# ESP8266_RFID_Schematic.net
KiCad netlist of a schematic drawn in EAGLE
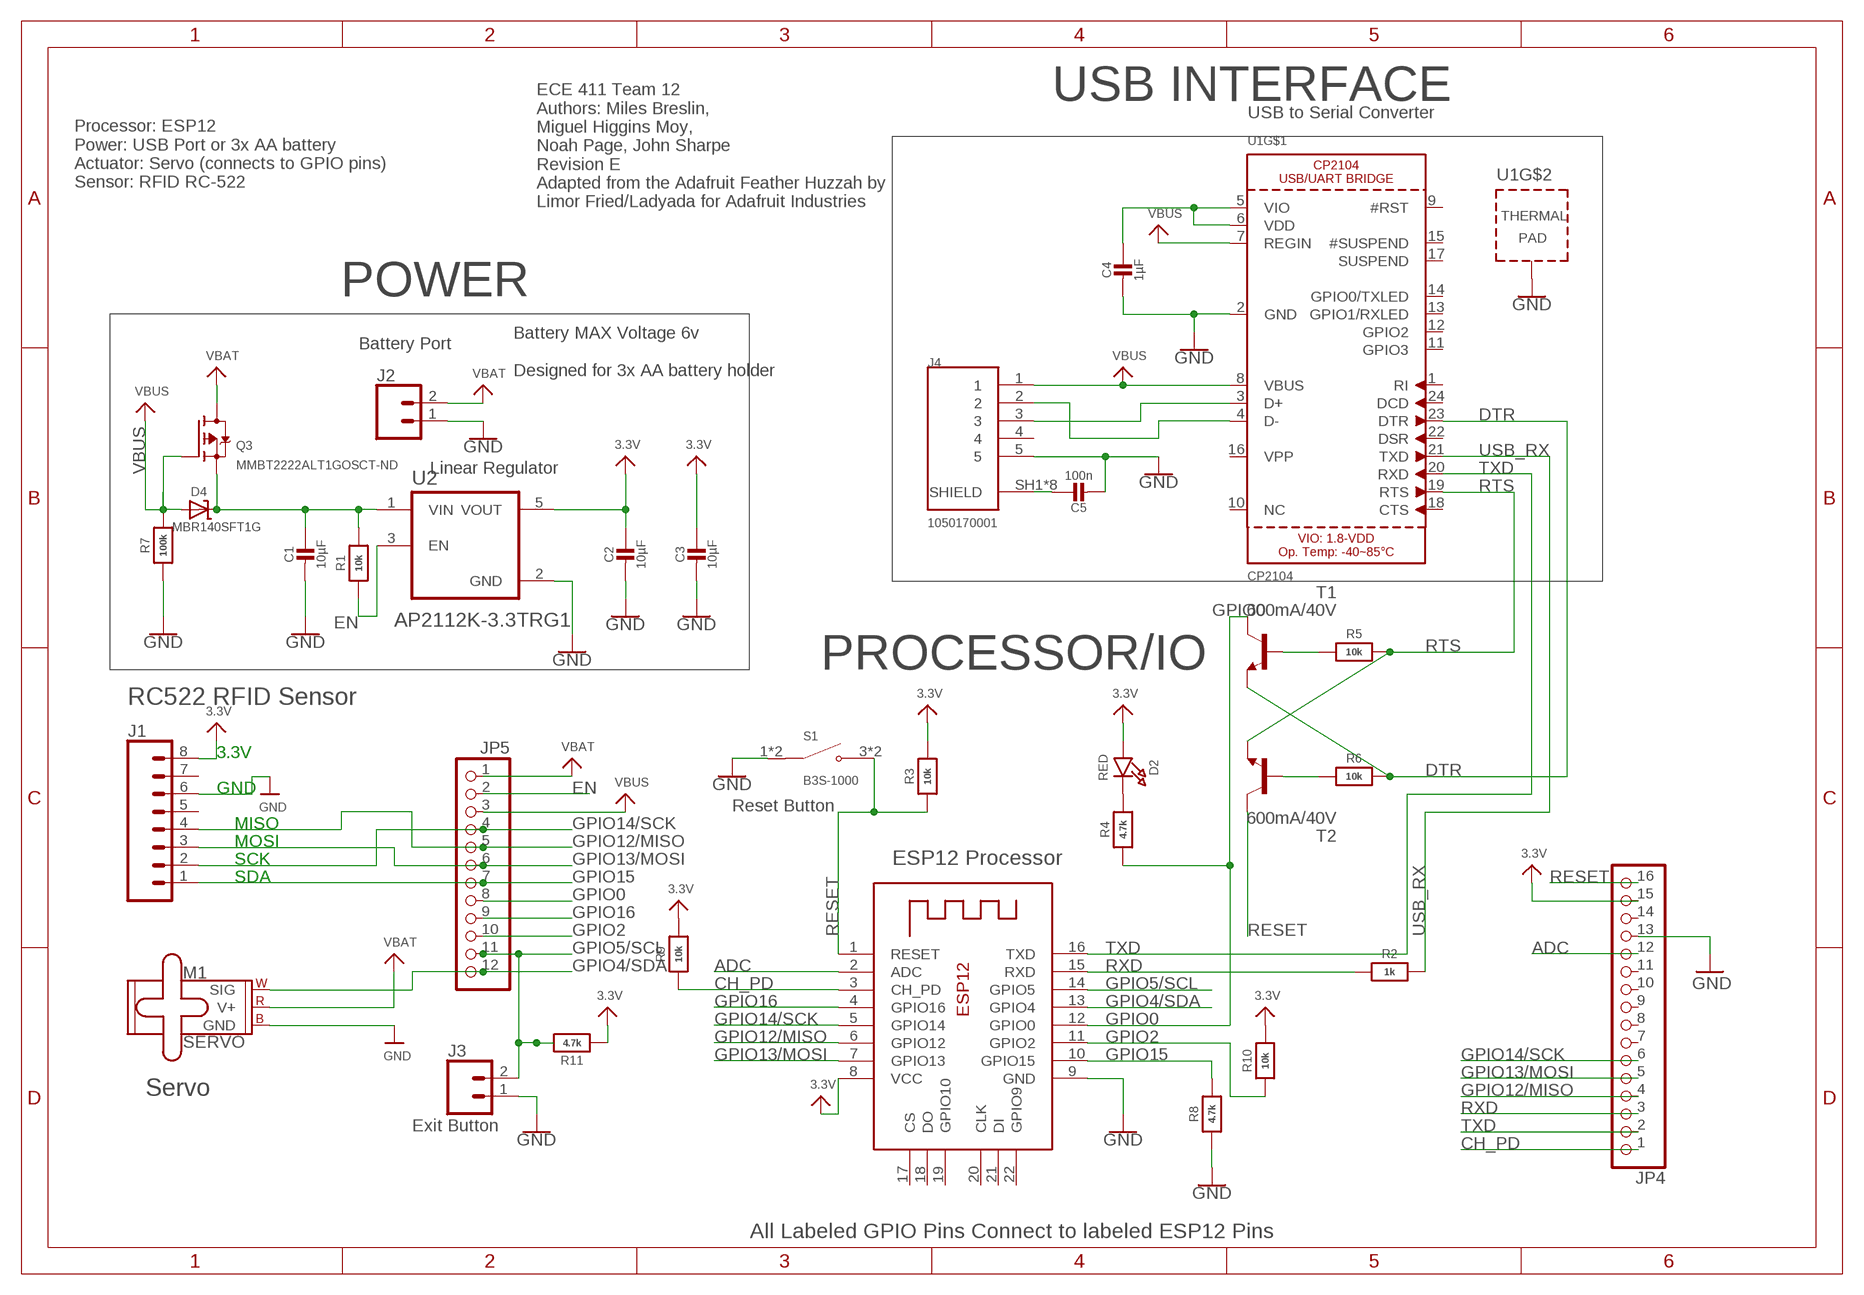
[diagram p0: schematic, sheet 1]

(export (version "E")
  (design (tool "Eeschema 10.0.6"))
  (components
    (comp (ref "C1")
      (value "10µF")
      (footprint "eagle-import:0603-MINI")
      (libsource (lib "eagle-import") (part "CAP_CERAMIC0603MINI"))
    )
    (comp (ref "C2")
      (value "10µF")
      (footprint "eagle-import:0603-MINI")
      (libsource (lib "eagle-import") (part "CAP_CERAMIC0603MINI"))
    )
    (comp (ref "C3")
      (value "10µF")
      (footprint "eagle-import:0603-MINI")
      (libsource (lib "eagle-import") (part "CAP_CERAMIC0603MINI"))
    )
    (comp (ref "C4")
      (value "1µF")
      (footprint "eagle-import:0603-MINI")
      (libsource (lib "eagle-import") (part "CAP_CERAMIC0603MINI"))
    )
    (comp (ref "C5")
      (value "100n")
      (footprint "eagle-import:0603-MINI")
      (libsource (lib "eagle-import") (part "CAP_CERAMIC0603MINI"))
    )
    (comp (ref "D2")
      (value "RED")
      (footprint "eagle-import:CHIPLED_0603")
      (libsource (lib "eagle-import") (part "LED0603"))
    )
    (comp (ref "D4")
      (value "MBR140SFT1G")
      (footprint "eagle-import:SOD-123")
      (libsource (lib "eagle-import") (part "DIODE-SCHOTTKYSOD-123"))
    )
    (comp (ref "J1")
      (value "CONN_08\"")
      (footprint "eagle-import:1X08")
      (libsource (lib "eagle-import") (part "CONN_08{dblquote}"))
    )
    (comp (ref "J2")
      (value "CONN_02")
      (footprint "eagle-import:1X02")
      (libsource (lib "eagle-import") (part "CONN_02"))
    )
    (comp (ref "J3")
      (value "CONN_02")
      (footprint "eagle-import:1X02")
      (libsource (lib "eagle-import") (part "CONN_02"))
    )
    (comp (ref "J4")
      (value "1050170001")
      (footprint "eagle-import:MOLEX_1050170001")
      (fields (field (name "DIGI-KEY_PART_NUMBER") "WM1399CT-ND") (field (name "MF") "Molex"))
      (libsource (lib "eagle-import") (part "1050170001"))
    )
    (comp (ref "JP4")
      (value "HEADER-1X16ROUND")
      (footprint "eagle-import:1X16_ROUND")
      (libsource (lib "eagle-import") (part "HEADER-1X16ROUND"))
    )
    (comp (ref "JP5")
      (value "HEADER-1X12")
      (footprint "eagle-import:1X12_ROUND")
      (libsource (lib "eagle-import") (part "HEADER-1X12"))
    )
    (comp (ref "M1")
      (value "SERVO")
      (footprint "eagle-import:1X03")
      (libsource (lib "eagle-import") (part "SERVO"))
    )
    (comp (ref "Q3")
      (value "MMBT2222ALT1GOSCT-ND")
      (footprint "eagle-import:SOT23-R")
      (libsource (lib "eagle-import") (part "MOSFET-P"))
    )
    (comp (ref "R1")
      (value "10k")
      (footprint "eagle-import:0603-MINI")
      (libsource (lib "eagle-import") (part "RESISTOR0603MINI"))
    )
    (comp (ref "R2")
      (value "1k")
      (footprint "eagle-import:0603-MINI")
      (libsource (lib "eagle-import") (part "RESISTOR0603MINI"))
    )
    (comp (ref "R3")
      (value "10k")
      (footprint "eagle-import:0603-MINI")
      (libsource (lib "eagle-import") (part "RESISTOR0603MINI"))
    )
    (comp (ref "R4")
      (value "4.7k")
      (footprint "eagle-import:0603-MINI")
      (libsource (lib "eagle-import") (part "RESISTOR0603MINI"))
    )
    (comp (ref "R5")
      (value "10k")
      (footprint "eagle-import:0603-MINI")
      (libsource (lib "eagle-import") (part "RESISTOR0603MINI"))
    )
    (comp (ref "R6")
      (value "10k")
      (footprint "eagle-import:0603-MINI")
      (libsource (lib "eagle-import") (part "RESISTOR0603MINI"))
    )
    (comp (ref "R7")
      (value "100k")
      (footprint "eagle-import:0603-MINI")
      (libsource (lib "eagle-import") (part "RESISTOR0603MINI"))
    )
    (comp (ref "R8")
      (value "4.7k")
      (footprint "eagle-import:0603-MINI")
      (libsource (lib "eagle-import") (part "RESISTOR0603MINI"))
    )
    (comp (ref "R9")
      (value "10k")
      (footprint "eagle-import:0603-MINI")
      (libsource (lib "eagle-import") (part "RESISTOR0603MINI"))
    )
    (comp (ref "R10")
      (value "10k")
      (footprint "eagle-import:0603-MINI")
      (libsource (lib "eagle-import") (part "RESISTOR0603MINI"))
    )
    (comp (ref "R11")
      (value "4.7k")
      (footprint "eagle-import:0603-MINI")
      (libsource (lib "eagle-import") (part "RESISTOR0603MINI"))
    )
    (comp (ref "S1")
      (value "B3S-1000")
      (footprint "eagle-import:SW_B3S-1000")
      (fields (field (name "DIGI-KEY_PART_NUMBER") "SW836TR-ND") (field (name "MF") "Omron"))
      (libsource (lib "eagle-import") (part "B3S-1000"))
    )
    (comp (ref "T1")
      (value "600mA/40V")
      (footprint "eagle-import:SOT23-3")
      (libsource (lib "eagle-import") (part "TRANS_NPN-MMBT2222AL"))
    )
    (comp (ref "T2")
      (value "600mA/40V")
      (footprint "eagle-import:SOT23-3")
      (libsource (lib "eagle-import") (part "TRANS_NPN-MMBT2222AL"))
    )
    (comp (ref "U1")
      (value "CP2104")
      (footprint "eagle-import:QFN24_4MM_SMSC")
      (libsource (lib "eagle-import") (part "CP2104"))
    )
    (comp (ref "U2")
      (value "AP2112K-3.3TRG1")
      (footprint "eagle-import:SOT95P285X140-5N")
      (fields
        (field (name "DIGI-KEY_PART_NUMBER") "AP2112K-3.3TRG1DICT-ND")
        (field (name "MF") "Diodes Inc.")
      )
      (libsource (lib "eagle-import") (part "AP2112K-3.3TRG1"))
    )
    (comp (ref "X1")
      (value "ESP-12E")
      (footprint "eagle-import:ESP-12E")
      (libsource (lib "eagle-import") (part "ESP-12E"))
    )
  )
  (nets
    (net (code "1") (name "/ADC") (class "Default")
      (node (ref "JP4") (pin "12") (pinfunction "12_12") (pintype "passive"))
      (node (ref "X1") (pin "2") (pinfunction "ADC_2") (pintype "passive"))
    )
    (net (code "2") (name "/CH_PD") (class "Default")
      (node (ref "JP4") (pin "1") (pinfunction "1_1") (pintype "passive"))
      (node (ref "R9") (pin "1") (pinfunction "1_1") (pintype "passive"))
      (node (ref "X1") (pin "3") (pinfunction "CH_PD_3") (pintype "input"))
    )
    (net (code "3") (name "/DTR") (class "Default")
      (node (ref "R6") (pin "2") (pinfunction "2_2") (pintype "passive"))
      (node (ref "T1") (pin "2") (pinfunction "E_2") (pintype "passive"))
      (node (ref "U1") (pin "23") (pinfunction "DTR_23") (pintype "output"))
    )
    (net (code "4") (name "/EN") (class "Default")
      (node (ref "JP5") (pin "2") (pinfunction "2_2") (pintype "passive"))
      (node (ref "R1") (pin "1") (pinfunction "1_1") (pintype "passive"))
      (node (ref "U2") (pin "3") (pinfunction "EN_3") (pintype "input"))
    )
    (net (code "5") (name "/GPIO0") (class "Default")
      (node (ref "JP5") (pin "8") (pinfunction "8_8") (pintype "passive"))
      (node (ref "R4") (pin "1") (pinfunction "1_1") (pintype "passive"))
      (node (ref "T1") (pin "3") (pinfunction "C_3") (pintype "passive"))
      (node (ref "X1") (pin "12") (pinfunction "GPIO0_12") (pintype "bidirectional"))
    )
    (net (code "6") (name "/GPIO2") (class "Default")
      (node (ref "JP5") (pin "10") (pinfunction "10_10") (pintype "passive"))
      (node (ref "R10") (pin "1") (pinfunction "1_1") (pintype "passive"))
      (node (ref "X1") (pin "11") (pinfunction "GPIO2_11") (pintype "bidirectional"))
    )
    (net (code "7") (name "/GPIO4{slash}SDA") (class "Default")
      (node (ref "JP5") (pin "12") (pinfunction "12_12") (pintype "passive"))
      (node (ref "M1") (pin "1") (pinfunction "SIG_1") (pintype "bidirectional"))
      (node (ref "X1") (pin "13") (pinfunction "GPIO4_13") (pintype "bidirectional"))
    )
    (net (code "8") (name "/GPIO5{slash}SCL") (class "Default")
      (node (ref "J3") (pin "2") (pinfunction "2_2") (pintype "passive"))
      (node (ref "JP5") (pin "11") (pinfunction "11_11") (pintype "passive"))
      (node (ref "R11") (pin "2") (pinfunction "2_2") (pintype "passive"))
      (node (ref "X1") (pin "14") (pinfunction "GPIO5_14") (pintype "bidirectional"))
    )
    (net (code "9") (name "/GPIO12{slash}MISO") (class "Default")
      (node (ref "J1") (pin "4") (pinfunction "4_4") (pintype "passive"))
      (node (ref "JP4") (pin "4") (pinfunction "4_4") (pintype "passive"))
      (node (ref "JP5") (pin "5") (pinfunction "5_5") (pintype "passive"))
      (node (ref "X1") (pin "6") (pinfunction "GPIO12_6") (pintype "bidirectional"))
    )
    (net (code "10") (name "/GPIO13{slash}MOSI") (class "Default")
      (node (ref "J1") (pin "3") (pinfunction "3_3") (pintype "passive"))
      (node (ref "JP4") (pin "5") (pinfunction "5_5") (pintype "passive"))
      (node (ref "JP5") (pin "6") (pinfunction "6_6") (pintype "passive"))
      (node (ref "X1") (pin "7") (pinfunction "GPIO13_7") (pintype "bidirectional"))
    )
    (net (code "11") (name "/GPIO14{slash}SCK") (class "Default")
      (node (ref "J1") (pin "2") (pinfunction "2_2") (pintype "passive"))
      (node (ref "JP4") (pin "6") (pinfunction "6_6") (pintype "passive"))
      (node (ref "JP5") (pin "4") (pinfunction "4_4") (pintype "passive"))
      (node (ref "X1") (pin "5") (pinfunction "GPIO14_5") (pintype "bidirectional"))
    )
    (net (code "12") (name "/GPIO15") (class "Default")
      (node (ref "J1") (pin "1") (pinfunction "1_1") (pintype "passive"))
      (node (ref "JP5") (pin "7") (pinfunction "7_7") (pintype "passive"))
      (node (ref "R8") (pin "2") (pinfunction "2_2") (pintype "passive"))
      (node (ref "X1") (pin "10") (pinfunction "GPIO15_10") (pintype "bidirectional"))
    )
    (net (code "13") (name "/GPIO16") (class "Default")
      (node (ref "JP5") (pin "9") (pinfunction "9_9") (pintype "passive"))
      (node (ref "X1") (pin "4") (pinfunction "GPIO16_4") (pintype "bidirectional"))
    )
    (net (code "14") (name "/RESET") (class "Default")
      (node (ref "JP4") (pin "16") (pinfunction "16_16") (pintype "passive"))
      (node (ref "R3") (pin "1") (pinfunction "1_1") (pintype "passive"))
      (node (ref "S1") (pin "3") (pinfunction "NO_3") (pintype "passive"))
      (node (ref "S1") (pin "4") (pinfunction "NO_4") (pintype "passive"))
      (node (ref "T2") (pin "3") (pinfunction "C_3") (pintype "passive"))
      (node (ref "X1") (pin "1") (pinfunction "RESET_1") (pintype "input"))
    )
    (net (code "15") (name "/RTS") (class "Default")
      (node (ref "R5") (pin "2") (pinfunction "2_2") (pintype "passive"))
      (node (ref "T2") (pin "2") (pinfunction "E_2") (pintype "passive"))
      (node (ref "U1") (pin "19") (pinfunction "RTS_19") (pintype "output"))
    )
    (net (code "16") (name "/RXD") (class "Default")
      (node (ref "JP4") (pin "3") (pinfunction "3_3") (pintype "passive"))
      (node (ref "R2") (pin "1") (pinfunction "1_1") (pintype "passive"))
      (node (ref "X1") (pin "15") (pinfunction "RXD_15") (pintype "input"))
    )
    (net (code "17") (name "/TXD") (class "Default")
      (node (ref "JP4") (pin "2") (pinfunction "2_2") (pintype "passive"))
      (node (ref "U1") (pin "20") (pinfunction "RXD_20") (pintype "input"))
      (node (ref "X1") (pin "16") (pinfunction "TXD_16") (pintype "output"))
    )
    (net (code "18") (name "/USB_RX") (class "Default")
      (node (ref "R2") (pin "2") (pinfunction "2_2") (pintype "passive"))
      (node (ref "U1") (pin "21") (pinfunction "TXD_21") (pintype "output"))
    )
    (net (code "19") (name "3.3V") (class "Default")
      (node (ref "C2") (pin "1") (pinfunction "1_1") (pintype "passive"))
      (node (ref "C3") (pin "1") (pinfunction "1_1") (pintype "passive"))
      (node (ref "D2") (pin "A") (pinfunction "A_A") (pintype "passive"))
      (node (ref "J1") (pin "8") (pinfunction "8_8") (pintype "passive"))
      (node (ref "JP4") (pin "15") (pinfunction "15_15") (pintype "passive"))
      (node (ref "R10") (pin "2") (pinfunction "2_2") (pintype "passive"))
      (node (ref "R11") (pin "1") (pinfunction "1_1") (pintype "passive"))
      (node (ref "R3") (pin "2") (pinfunction "2_2") (pintype "passive"))
      (node (ref "R9") (pin "2") (pinfunction "2_2") (pintype "passive"))
      (node (ref "U2") (pin "5") (pinfunction "VOUT_5") (pintype "power_in"))
      (node (ref "X1") (pin "8") (pinfunction "VCC_8") (pintype "power_in"))
    )
    (net (code "20") (name "GND") (class "Default")
      (node (ref "C1") (pin "2") (pinfunction "2_2") (pintype "passive"))
      (node (ref "C2") (pin "2") (pinfunction "2_2") (pintype "passive"))
      (node (ref "C3") (pin "2") (pinfunction "2_2") (pintype "passive"))
      (node (ref "C4") (pin "2") (pinfunction "2_2") (pintype "passive"))
      (node (ref "C5") (pin "2") (pinfunction "2_2") (pintype "passive"))
      (node (ref "J1") (pin "6") (pinfunction "6_6") (pintype "passive"))
      (node (ref "J2") (pin "1") (pinfunction "1_1") (pintype "passive"))
      (node (ref "J3") (pin "1") (pinfunction "1_1") (pintype "passive"))
      (node (ref "J4") (pin "5") (pinfunction "5_5") (pintype "passive"))
      (node (ref "JP4") (pin "13") (pinfunction "13_13") (pintype "passive"))
      (node (ref "M1") (pin "3") (pinfunction "GND_3") (pintype "bidirectional"))
      (node (ref "R7") (pin "1") (pinfunction "1_1") (pintype "passive"))
      (node (ref "R8") (pin "1") (pinfunction "1_1") (pintype "passive"))
      (node (ref "S1") (pin "1") (pinfunction "COM_1") (pintype "passive"))
      (node (ref "S1") (pin "2") (pinfunction "COM_2") (pintype "passive"))
      (node (ref "U1") (pin "2") (pinfunction "GND_2") (pintype "power_in"))
      (node (ref "U1") (pin "THERM") (pinfunction "TP_THERM") (pintype "power_in"))
      (node (ref "U2") (pin "2") (pinfunction "GND_2") (pintype "power_in"))
      (node (ref "X1") (pin "9") (pinfunction "GND_9") (pintype "power_in"))
    )
    (net (code "21") (name "Net-(C5-Pad1)") (class "Default")
      (node (ref "C5") (pin "1") (pinfunction "1_1") (pintype "passive"))
      (node (ref "J4") (pin "SH1") (pinfunction "SHIELD_SH1") (pintype "passive"))
      (node (ref "J4") (pin "SH2") (pinfunction "SHIELD_SH2") (pintype "passive"))
      (node (ref "J4") (pin "SH3") (pinfunction "SHIELD_SH3") (pintype "passive"))
      (node (ref "J4") (pin "SH4") (pinfunction "SHIELD_SH4") (pintype "passive"))
      (node (ref "J4") (pin "SH5") (pinfunction "SHIELD_SH5") (pintype "passive"))
      (node (ref "J4") (pin "SH6") (pinfunction "SHIELD_SH6") (pintype "passive"))
      (node (ref "J4") (pin "SH7") (pinfunction "SHIELD_SH7") (pintype "passive"))
      (node (ref "J4") (pin "SH8") (pinfunction "SHIELD_SH8") (pintype "passive"))
    )
    (net (code "22") (name "Net-(D2-PadC)") (class "Default")
      (node (ref "D2") (pin "C") (pinfunction "C_C") (pintype "passive"))
      (node (ref "R4") (pin "2") (pinfunction "2_2") (pintype "passive"))
    )
    (net (code "23") (name "Net-(Q3-S)") (class "Default")
      (node (ref "C1") (pin "1") (pinfunction "1_1") (pintype "passive"))
      (node (ref "D4") (pin "C") (pinfunction "C_C") (pintype "passive"))
      (node (ref "Q3") (pin "2") (pinfunction "S_2") (pintype "passive"))
      (node (ref "R1") (pin "2") (pinfunction "2_2") (pintype "passive"))
      (node (ref "U2") (pin "1") (pinfunction "VIN_1") (pintype "power_in"))
    )
    (net (code "24") (name "Net-(T1-B)") (class "Default")
      (node (ref "R5") (pin "1") (pinfunction "1_1") (pintype "passive"))
      (node (ref "T1") (pin "1") (pinfunction "B_1") (pintype "passive"))
    )
    (net (code "25") (name "Net-(T2-B)") (class "Default")
      (node (ref "R6") (pin "1") (pinfunction "1_1") (pintype "passive"))
      (node (ref "T2") (pin "1") (pinfunction "B_1") (pintype "passive"))
    )
    (net (code "26") (name "Net-(U1A-D+)") (class "Default")
      (node (ref "J4") (pin "3") (pinfunction "3_3") (pintype "passive"))
      (node (ref "U1") (pin "3") (pinfunction "D+_3") (pintype "bidirectional"))
    )
    (net (code "27") (name "Net-(U1A-D-)") (class "Default")
      (node (ref "J4") (pin "2") (pinfunction "2_2") (pintype "passive"))
      (node (ref "U1") (pin "4") (pinfunction "D-_4") (pintype "bidirectional"))
    )
    (net (code "28") (name "Net-(U1A-VDD)") (class "Default")
      (node (ref "C4") (pin "1") (pinfunction "1_1") (pintype "passive"))
      (node (ref "U1") (pin "5") (pinfunction "VIO_5") (pintype "power_in"))
      (node (ref "U1") (pin "6") (pinfunction "VDD_6") (pintype "power_in"))
    )
    (net (code "29") (name "VBAT") (class "Default")
      (node (ref "J2") (pin "2") (pinfunction "2_2") (pintype "passive"))
      (node (ref "JP5") (pin "1") (pinfunction "1_1") (pintype "passive"))
      (node (ref "M1") (pin "2") (pinfunction "V+_2") (pintype "bidirectional"))
      (node (ref "Q3") (pin "3") (pinfunction "D_3") (pintype "passive"))
    )
    (net (code "30") (name "VBUS") (class "Default")
      (node (ref "D4") (pin "A") (pinfunction "A_A") (pintype "passive"))
      (node (ref "J4") (pin "1") (pinfunction "1_1") (pintype "passive"))
      (node (ref "JP5") (pin "3") (pinfunction "3_3") (pintype "passive"))
      (node (ref "Q3") (pin "1") (pinfunction "G_1") (pintype "passive"))
      (node (ref "R7") (pin "2") (pinfunction "2_2") (pintype "passive"))
      (node (ref "U1") (pin "7") (pinfunction "REGIN_7") (pintype "power_in"))
      (node (ref "U1") (pin "8") (pinfunction "VBUS_8") (pintype "power_in"))
    )
    (net (code "31") (name "unconnected-(J1-Pad5)") (class "Default")
      (node (ref "J1") (pin "5") (pinfunction "5_5") (pintype "passive"))
    )
    (net (code "32") (name "unconnected-(J1-Pad7)") (class "Default")
      (node (ref "J1") (pin "7") (pinfunction "7_7") (pintype "passive"))
    )
    (net (code "33") (name "unconnected-(J4-Pad4)") (class "Default")
      (node (ref "J4") (pin "4") (pinfunction "4_4") (pintype "passive"))
    )
    (net (code "34") (name "unconnected-(JP4-Pad7)") (class "Default")
      (node (ref "JP4") (pin "7") (pinfunction "7_7") (pintype "passive"))
    )
    (net (code "35") (name "unconnected-(JP4-Pad8)") (class "Default")
      (node (ref "JP4") (pin "8") (pinfunction "8_8") (pintype "passive"))
    )
    (net (code "36") (name "unconnected-(JP4-Pad9)") (class "Default")
      (node (ref "JP4") (pin "9") (pinfunction "9_9") (pintype "passive"))
    )
    (net (code "37") (name "unconnected-(JP4-Pad10)") (class "Default")
      (node (ref "JP4") (pin "10") (pinfunction "10_10") (pintype "passive"))
    )
    (net (code "38") (name "unconnected-(JP4-Pad11)") (class "Default")
      (node (ref "JP4") (pin "11") (pinfunction "11_11") (pintype "passive"))
    )
    (net (code "39") (name "unconnected-(JP4-Pad14)") (class "Default")
      (node (ref "JP4") (pin "14") (pinfunction "14_14") (pintype "passive"))
    )
    (net (code "40") (name "unconnected-(U1A-#RST-Pad9)") (class "Default")
      (node (ref "U1") (pin "9") (pinfunction "#RST_9") (pintype "bidirectional"))
    )
    (net (code "41") (name "unconnected-(U1A-#SUSPEND-Pad15)") (class "Default")
      (node (ref "U1") (pin "15") (pinfunction "#SUSPEND_15") (pintype "output"))
    )
    (net (code "42") (name "unconnected-(U1A-CTS-Pad18)") (class "Default")
      (node (ref "U1") (pin "18") (pinfunction "CTS_18") (pintype "input"))
    )
    (net (code "43") (name "unconnected-(U1A-DCD-Pad24)") (class "Default")
      (node (ref "U1") (pin "24") (pinfunction "DCD_24") (pintype "input"))
    )
    (net (code "44") (name "unconnected-(U1A-DSR-Pad22)") (class "Default")
      (node (ref "U1") (pin "22") (pinfunction "DSR_22") (pintype "input"))
    )
    (net (code "45") (name "unconnected-(U1A-GPIO0{slash}TXLED-Pad14)") (class "Default")
      (node (ref "U1") (pin "14") (pinfunction "GPIO0/TXLED_14") (pintype "bidirectional"))
    )
    (net (code "46") (name "unconnected-(U1A-GPIO1{slash}RXLED-Pad13)") (class "Default")
      (node (ref "U1") (pin "13") (pinfunction "GPIO1/RXLED_13") (pintype "bidirectional"))
    )
    (net (code "47") (name "unconnected-(U1A-GPIO2-Pad12)") (class "Default")
      (node (ref "U1") (pin "12") (pinfunction "GPIO2_12") (pintype "bidirectional"))
    )
    (net (code "48") (name "unconnected-(U1A-GPIO3-Pad11)") (class "Default")
      (node (ref "U1") (pin "11") (pinfunction "GPIO3_11") (pintype "bidirectional"))
    )
    (net (code "49") (name "unconnected-(U1A-NC-Pad10)") (class "Default")
      (node (ref "U1") (pin "10") (pinfunction "NC_10") (pintype "no_connect"))
    )
    (net (code "50") (name "unconnected-(U1A-RI-Pad1)") (class "Default")
      (node (ref "U1") (pin "1") (pinfunction "RI_1") (pintype "input"))
    )
    (net (code "51") (name "unconnected-(U1A-SUSPEND-Pad17)") (class "Default")
      (node (ref "U1") (pin "17") (pinfunction "SUSPEND_17") (pintype "output"))
    )
    (net (code "52") (name "unconnected-(U1A-VPP-Pad16)") (class "Default")
      (node (ref "U1") (pin "16") (pinfunction "VPP_16") (pintype "bidirectional"))
    )
    (net (code "53") (name "unconnected-(X1-CLK-Pad20)") (class "Default")
      (node (ref "X1") (pin "20") (pinfunction "CLK_20") (pintype "bidirectional"))
    )
    (net (code "54") (name "unconnected-(X1-CS-Pad17)") (class "Default")
      (node (ref "X1") (pin "17") (pinfunction "CS_17") (pintype "bidirectional"))
    )
    (net (code "55") (name "unconnected-(X1-DI-Pad21)") (class "Default")
      (node (ref "X1") (pin "21") (pinfunction "DI_21") (pintype "bidirectional"))
    )
    (net (code "56") (name "unconnected-(X1-DO-Pad18)") (class "Default")
      (node (ref "X1") (pin "18") (pinfunction "DO_18") (pintype "bidirectional"))
    )
    (net (code "57") (name "unconnected-(X1-GPIO9-Pad22)") (class "Default")
      (node (ref "X1") (pin "22") (pinfunction "GPIO9_22") (pintype "bidirectional"))
    )
    (net (code "58") (name "unconnected-(X1-GPIO10-Pad19)") (class "Default")
      (node (ref "X1") (pin "19") (pinfunction "GPIO10_19") (pintype "bidirectional"))
    )
  )
)
